# external_strip_v4.net
KiCad netlist of a schematic drawn in EAGLE
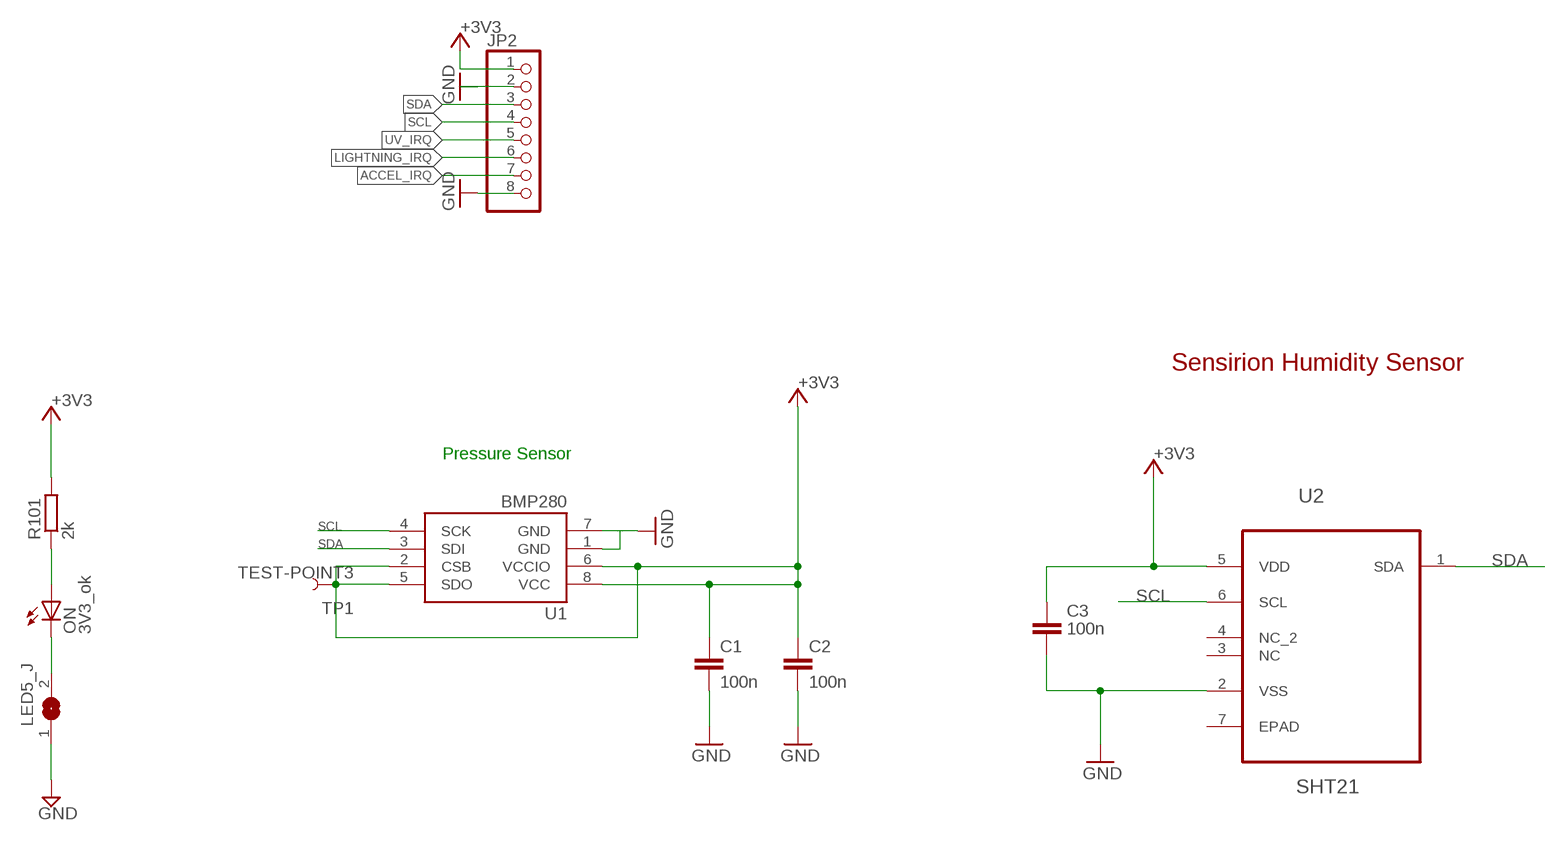
[diagram p0: schematic, sheet 1, part 1 of 2]
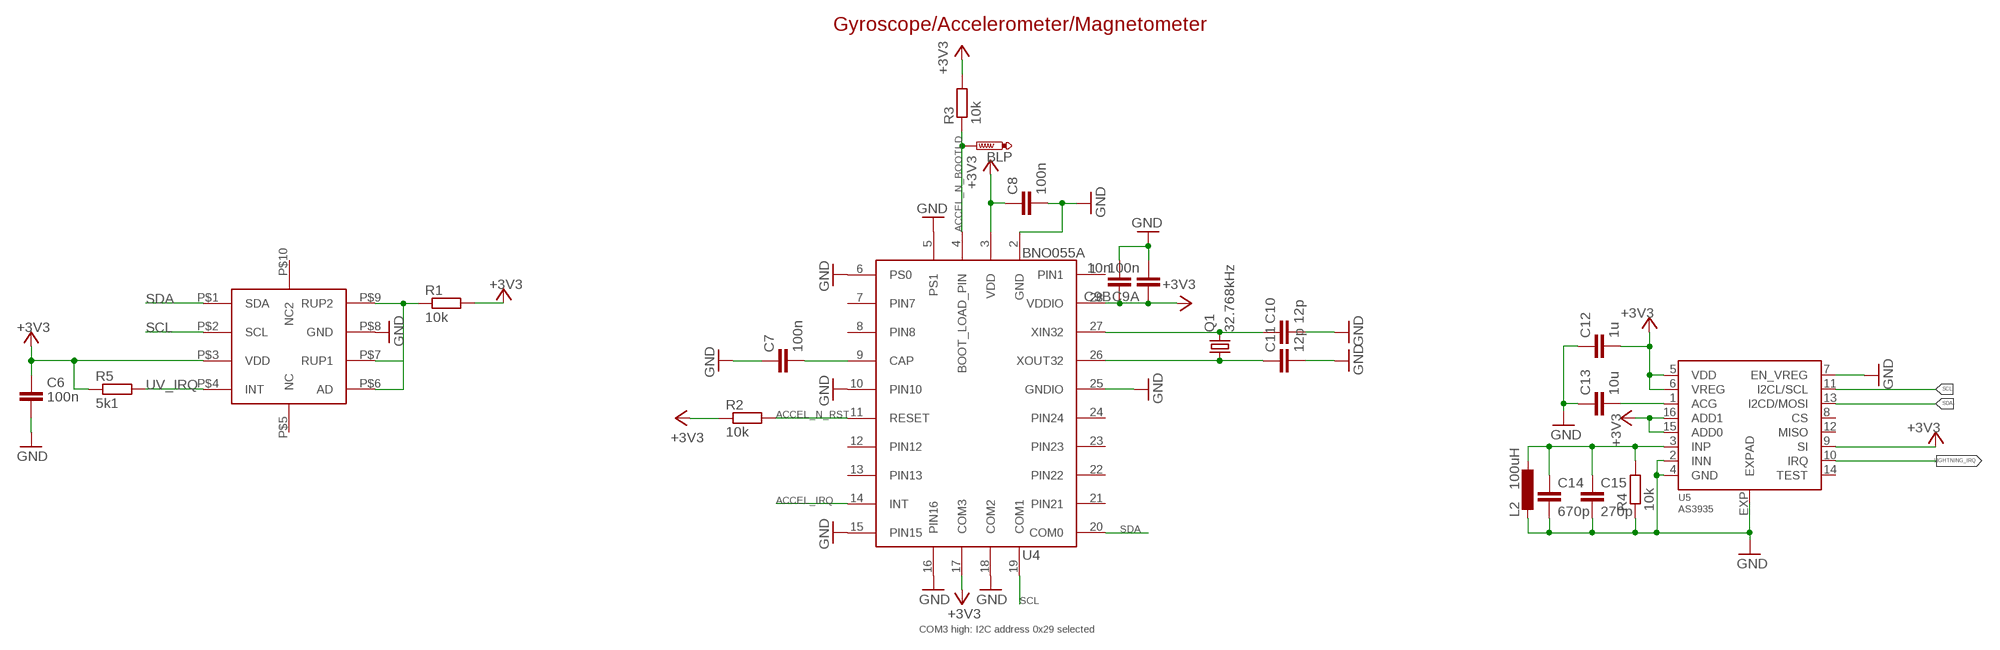
[diagram p1: schematic, sheet 1, part 2 of 2]

(export (version "E")
  (design (tool "Eeschema 10.0.6"))
  (components
    (comp (ref "BLP")
      (value "PTR1B1,27")
      (footprint "eagle-import:B1,27")
      (libsource (lib "eagle-import") (part "PTR1B1,27"))
    )
    (comp (ref "C1")
      (value "100n")
      (footprint "eagle-import:C0603")
      (libsource (lib "eagle-import") (part "C-EUC0603"))
    )
    (comp (ref "C2")
      (value "100n")
      (footprint "eagle-import:C0603")
      (libsource (lib "eagle-import") (part "C-EUC0603"))
    )
    (comp (ref "C3")
      (value "100n")
      (footprint "eagle-import:C0603")
      (libsource (lib "eagle-import") (part "C-EUC0603"))
    )
    (comp (ref "C6")
      (value "100n")
      (footprint "eagle-import:C0603")
      (libsource (lib "eagle-import") (part "C-EUC0603"))
    )
    (comp (ref "C7")
      (value "100n")
      (footprint "eagle-import:C0603")
      (libsource (lib "eagle-import") (part "C-EUC0603"))
    )
    (comp (ref "C8")
      (value "100n")
      (footprint "eagle-import:C0603")
      (libsource (lib "eagle-import") (part "C-EUC0603"))
    )
    (comp (ref "C9A")
      (value "100n")
      (footprint "eagle-import:C0603")
      (libsource (lib "eagle-import") (part "C-EUC0603"))
    )
    (comp (ref "C9B")
      (value "10n")
      (footprint "eagle-import:C0603")
      (libsource (lib "eagle-import") (part "C-EUC0603"))
    )
    (comp (ref "C10")
      (value "12p")
      (footprint "eagle-import:C0603")
      (libsource (lib "eagle-import") (part "C-EUC0603"))
    )
    (comp (ref "C11")
      (value "12p")
      (footprint "eagle-import:C0603")
      (libsource (lib "eagle-import") (part "C-EUC0603"))
    )
    (comp (ref "C12")
      (value "1u")
      (footprint "eagle-import:C0603")
      (libsource (lib "eagle-import") (part "C-EUC0603"))
    )
    (comp (ref "C13")
      (value "10u")
      (footprint "eagle-import:C0603")
      (libsource (lib "eagle-import") (part "C-EUC0603"))
    )
    (comp (ref "C14")
      (value "670p")
      (footprint "eagle-import:C0603")
      (libsource (lib "eagle-import") (part "C-EUC0603"))
    )
    (comp (ref "C15")
      (value "270p")
      (footprint "eagle-import:C0603")
      (libsource (lib "eagle-import") (part "C-EUC0603"))
    )
    (comp (ref "JP2")
      (value "PINHD-1X8")
      (footprint "eagle-import:1X08")
      (libsource (lib "eagle-import") (part "PINHD-1X8"))
    )
    (comp (ref "L2")
      (value "100uH")
      (footprint "eagle-import:COILCRAFT")
      (libsource (lib "eagle-import") (part "COILCRAFT"))
    )
    (comp (ref "LED5_J")
      (value "SJ")
      (footprint "eagle-import:SJ")
      (libsource (lib "eagle-import") (part "SJ"))
    )
    (comp (ref "ON")
      (value "3V3_ok")
      (footprint "eagle-import:CHIPLED_0603")
      (libsource (lib "eagle-import") (part "LEDCHIPLED_0603"))
    )
    (comp (ref "Q1")
      (value "32.768kHz")
      (footprint "eagle-import:FC-12M")
      (libsource (lib "eagle-import") (part "FC-12M"))
    )
    (comp (ref "R1")
      (value "10k")
      (footprint "eagle-import:R0603")
      (libsource (lib "eagle-import") (part "R-EU_R0603"))
    )
    (comp (ref "R2")
      (value "10k")
      (footprint "eagle-import:R0603")
      (libsource (lib "eagle-import") (part "R-EU_R0603"))
    )
    (comp (ref "R3")
      (value "10k")
      (footprint "eagle-import:R0603")
      (libsource (lib "eagle-import") (part "R-EU_R0603"))
    )
    (comp (ref "R4")
      (value "10k")
      (footprint "eagle-import:R0603")
      (libsource (lib "eagle-import") (part "resistor_R-EU_R0603"))
    )
    (comp (ref "R5")
      (value "5k1")
      (footprint "eagle-import:R0603")
      (libsource (lib "eagle-import") (part "R-EU_R0603"))
    )
    (comp (ref "R101")
      (value "2k")
      (footprint "eagle-import:R0603")
      (libsource (lib "eagle-import") (part "R-EU_R0603"))
    )
    (comp (ref "TP1")
      (value "TEST-POINT3")
      (footprint "eagle-import:PAD.03X.03")
      (libsource (lib "eagle-import") (part "TEST-POINT3"))
    )
    (comp (ref "U1")
      (value "BMP280")
      (footprint "eagle-import:LGA8")
      (libsource (lib "eagle-import") (part "BMP280"))
    )
    (comp (ref "U2")
      (value "SHT21")
      (footprint "eagle-import:DFN300X300X110-7N")
      (libsource (lib "eagle-import") (part "SHT21"))
    )
    (comp (ref "U3")
      (value "SI1133")
      (footprint "eagle-import:DFN2X2")
      (libsource (lib "eagle-import") (part "SI1133"))
    )
    (comp (ref "U4")
      (value "BNO055A")
      (footprint "eagle-import:BNO055")
      (libsource (lib "eagle-import") (part "BNO055A"))
    )
    (comp (ref "U5")
      (value "AS3935")
      (footprint "eagle-import:16LDMLPQ")
      (libsource (lib "eagle-import") (part "AS3935"))
    )
  )
  (nets
    (net (code "1") (name "+3V3") (class "Default")
      (node (ref "C1") (pin "1") (pinfunction "1_1") (pintype "passive"))
      (node (ref "C12") (pin "2") (pinfunction "2_2") (pintype "passive"))
      (node (ref "C2") (pin "1") (pinfunction "1_1") (pintype "passive"))
      (node (ref "C3") (pin "1") (pinfunction "1_1") (pintype "passive"))
      (node (ref "C6") (pin "1") (pinfunction "1_1") (pintype "passive"))
      (node (ref "C8") (pin "1") (pinfunction "1_1") (pintype "passive"))
      (node (ref "C9A") (pin "1") (pinfunction "1_1") (pintype "passive"))
      (node (ref "C9B") (pin "1") (pinfunction "1_1") (pintype "passive"))
      (node (ref "JP2") (pin "1") (pinfunction "1_1") (pintype "passive"))
      (node (ref "R1") (pin "2") (pinfunction "2_2") (pintype "passive"))
      (node (ref "R101") (pin "2") (pinfunction "2_2") (pintype "passive"))
      (node (ref "R2") (pin "1") (pinfunction "1_1") (pintype "passive"))
      (node (ref "R3") (pin "2") (pinfunction "2_2") (pintype "passive"))
      (node (ref "R5") (pin "1") (pinfunction "1_1") (pintype "passive"))
      (node (ref "TP1") (pin "P$1") (pinfunction "1_P$1") (pintype "bidirectional"))
      (node (ref "U1") (pin "2") (pinfunction "CSB_2") (pintype "input"))
      (node (ref "U1") (pin "5") (pinfunction "SDO_5") (pintype "bidirectional"))
      (node (ref "U1") (pin "6") (pinfunction "VCCIO_6") (pintype "power_in"))
      (node (ref "U1") (pin "8") (pinfunction "VCC_8") (pintype "power_in"))
      (node (ref "U2") (pin "5") (pinfunction "VDD_5") (pintype "power_in"))
      (node (ref "U3") (pin "P$3") (pinfunction "VDD_P$3") (pintype "bidirectional"))
      (node (ref "U4") (pin "17") (pinfunction "COM3_17") (pintype "bidirectional"))
      (node (ref "U4") (pin "28") (pinfunction "VDDIO_28") (pintype "bidirectional"))
      (node (ref "U4") (pin "3") (pinfunction "VDD_3") (pintype "bidirectional"))
      (node (ref "U5") (pin "15") (pinfunction "ADD0_15") (pintype "bidirectional"))
      (node (ref "U5") (pin "16") (pinfunction "ADD1_16") (pintype "bidirectional"))
      (node (ref "U5") (pin "5") (pinfunction "VDD_5") (pintype "bidirectional"))
      (node (ref "U5") (pin "6") (pinfunction "VREG_6") (pintype "bidirectional"))
      (node (ref "U5") (pin "9") (pinfunction "SI_9") (pintype "bidirectional"))
    )
    (net (code "2") (name "/ACCEL_N_BOOTLD") (class "Default")
      (node (ref "BLP") (pin "TP") (pinfunction "TP_TP") (pintype "input"))
      (node (ref "R3") (pin "1") (pinfunction "1_1") (pintype "passive"))
      (node (ref "U4") (pin "4") (pinfunction "BOOT_LOAD_PIN_4") (pintype "bidirectional"))
    )
    (net (code "3") (name "/ACCEL_N_RST") (class "Default")
      (node (ref "R2") (pin "2") (pinfunction "2_2") (pintype "passive"))
      (node (ref "U4") (pin "11") (pinfunction "RESET_11") (pintype "bidirectional"))
    )
    (net (code "4") (name "ACCEL_IRQ") (class "Default")
      (node (ref "JP2") (pin "7") (pinfunction "7_7") (pintype "passive"))
      (node (ref "U4") (pin "14") (pinfunction "INT_14") (pintype "bidirectional"))
    )
    (net (code "5") (name "GND") (class "Default")
      (node (ref "C1") (pin "2") (pinfunction "2_2") (pintype "passive"))
      (node (ref "C10") (pin "2") (pinfunction "2_2") (pintype "passive"))
      (node (ref "C11") (pin "2") (pinfunction "2_2") (pintype "passive"))
      (node (ref "C12") (pin "1") (pinfunction "1_1") (pintype "passive"))
      (node (ref "C13") (pin "1") (pinfunction "1_1") (pintype "passive"))
      (node (ref "C14") (pin "2") (pinfunction "2_2") (pintype "passive"))
      (node (ref "C15") (pin "2") (pinfunction "2_2") (pintype "passive"))
      (node (ref "C2") (pin "2") (pinfunction "2_2") (pintype "passive"))
      (node (ref "C3") (pin "2") (pinfunction "2_2") (pintype "passive"))
      (node (ref "C6") (pin "2") (pinfunction "2_2") (pintype "passive"))
      (node (ref "C7") (pin "1") (pinfunction "1_1") (pintype "passive"))
      (node (ref "C8") (pin "2") (pinfunction "2_2") (pintype "passive"))
      (node (ref "C9A") (pin "2") (pinfunction "2_2") (pintype "passive"))
      (node (ref "C9B") (pin "2") (pinfunction "2_2") (pintype "passive"))
      (node (ref "JP2") (pin "2") (pinfunction "2_2") (pintype "passive"))
      (node (ref "JP2") (pin "8") (pinfunction "8_8") (pintype "passive"))
      (node (ref "L2") (pin "2") (pinfunction "2_2") (pintype "passive"))
      (node (ref "LED5_J") (pin "1") (pinfunction "1_1") (pintype "passive"))
      (node (ref "R4") (pin "1") (pinfunction "1_1") (pintype "passive"))
      (node (ref "U1") (pin "1") (pinfunction "GND_1") (pintype "power_in"))
      (node (ref "U1") (pin "7") (pinfunction "GND_7") (pintype "power_in"))
      (node (ref "U2") (pin "2") (pinfunction "VSS_2") (pintype "power_in"))
      (node (ref "U3") (pin "P$8") (pinfunction "GND_P$8") (pintype "bidirectional"))
      (node (ref "U4") (pin "10") (pinfunction "PIN10_10") (pintype "bidirectional"))
      (node (ref "U4") (pin "15") (pinfunction "PIN15_15") (pintype "bidirectional"))
      (node (ref "U4") (pin "16") (pinfunction "PIN16_16") (pintype "bidirectional"))
      (node (ref "U4") (pin "18") (pinfunction "COM2_18") (pintype "bidirectional"))
      (node (ref "U4") (pin "2") (pinfunction "GND_2") (pintype "bidirectional"))
      (node (ref "U4") (pin "25") (pinfunction "GNDIO_25") (pintype "bidirectional"))
      (node (ref "U4") (pin "5") (pinfunction "PS1_5") (pintype "bidirectional"))
      (node (ref "U4") (pin "6") (pinfunction "PS0_6") (pintype "bidirectional"))
      (node (ref "U5") (pin "2") (pinfunction "INN_2") (pintype "bidirectional"))
      (node (ref "U5") (pin "4") (pinfunction "GND_4") (pintype "bidirectional"))
      (node (ref "U5") (pin "7") (pinfunction "EN_VREG_7") (pintype "bidirectional"))
      (node (ref "U5") (pin "EXP") (pinfunction "EXPAD_EXP") (pintype "bidirectional"))
    )
    (net (code "6") (name "LIGHTNING_IRQ") (class "Default")
      (node (ref "JP2") (pin "6") (pinfunction "6_6") (pintype "passive"))
      (node (ref "U5") (pin "10") (pinfunction "IRQ_10") (pintype "bidirectional"))
    )
    (net (code "7") (name "Net-(LED5_J-Pad2)") (class "Default")
      (node (ref "LED5_J") (pin "2") (pinfunction "2_2") (pintype "passive"))
      (node (ref "ON") (pin "C") (pinfunction "C_C") (pintype "passive"))
    )
    (net (code "8") (name "Net-(ON-PadA)") (class "Default")
      (node (ref "ON") (pin "A") (pinfunction "A_A") (pintype "passive"))
      (node (ref "R101") (pin "1") (pinfunction "1_1") (pintype "passive"))
    )
    (net (code "9") (name "Net-(U3-AD)") (class "Default")
      (node (ref "R1") (pin "1") (pinfunction "1_1") (pintype "passive"))
      (node (ref "U3") (pin "P$6") (pinfunction "AD_P$6") (pintype "bidirectional"))
      (node (ref "U3") (pin "P$7") (pinfunction "RUP1_P$7") (pintype "bidirectional"))
      (node (ref "U3") (pin "P$9") (pinfunction "RUP2_P$9") (pintype "bidirectional"))
    )
    (net (code "10") (name "Net-(U4-CAP)") (class "Default")
      (node (ref "C7") (pin "2") (pinfunction "2_2") (pintype "passive"))
      (node (ref "U4") (pin "9") (pinfunction "CAP_9") (pintype "bidirectional"))
    )
    (net (code "11") (name "Net-(U4-XIN32)") (class "Default")
      (node (ref "C10") (pin "1") (pinfunction "1_1") (pintype "passive"))
      (node (ref "Q1") (pin "2") (pinfunction "2_2") (pintype "passive"))
      (node (ref "U4") (pin "27") (pinfunction "XIN32_27") (pintype "bidirectional"))
    )
    (net (code "12") (name "Net-(U4-XOUT32)") (class "Default")
      (node (ref "C11") (pin "1") (pinfunction "1_1") (pintype "passive"))
      (node (ref "Q1") (pin "1") (pinfunction "1_1") (pintype "passive"))
      (node (ref "U4") (pin "26") (pinfunction "XOUT32_26") (pintype "bidirectional"))
    )
    (net (code "13") (name "Net-(U5-ACG)") (class "Default")
      (node (ref "C13") (pin "2") (pinfunction "2_2") (pintype "passive"))
      (node (ref "U5") (pin "1") (pinfunction "ACG_1") (pintype "bidirectional"))
    )
    (net (code "14") (name "Net-(U5-INP)") (class "Default")
      (node (ref "C14") (pin "1") (pinfunction "1_1") (pintype "passive"))
      (node (ref "C15") (pin "1") (pinfunction "1_1") (pintype "passive"))
      (node (ref "L2") (pin "1") (pinfunction "1_1") (pintype "passive"))
      (node (ref "R4") (pin "2") (pinfunction "2_2") (pintype "passive"))
      (node (ref "U5") (pin "3") (pinfunction "INP_3") (pintype "bidirectional"))
    )
    (net (code "15") (name "SCL") (class "Default")
      (node (ref "JP2") (pin "4") (pinfunction "4_4") (pintype "passive"))
      (node (ref "U1") (pin "4") (pinfunction "SCK_4") (pintype "bidirectional"))
      (node (ref "U2") (pin "6") (pinfunction "SCL_6") (pintype "input"))
      (node (ref "U3") (pin "P$2") (pinfunction "SCL_P$2") (pintype "bidirectional"))
      (node (ref "U4") (pin "19") (pinfunction "COM1_19") (pintype "bidirectional"))
      (node (ref "U5") (pin "11") (pinfunction "I2CL/SCL_11") (pintype "bidirectional"))
    )
    (net (code "16") (name "SDA") (class "Default")
      (node (ref "JP2") (pin "3") (pinfunction "3_3") (pintype "passive"))
      (node (ref "U1") (pin "3") (pinfunction "SDI_3") (pintype "bidirectional"))
      (node (ref "U2") (pin "1") (pinfunction "SDA_1") (pintype "bidirectional"))
      (node (ref "U3") (pin "P$1") (pinfunction "SDA_P$1") (pintype "bidirectional"))
      (node (ref "U4") (pin "20") (pinfunction "COM0_20") (pintype "bidirectional"))
      (node (ref "U5") (pin "13") (pinfunction "I2CD/MOSI_13") (pintype "bidirectional"))
    )
    (net (code "17") (name "UV_IRQ") (class "Default")
      (node (ref "JP2") (pin "5") (pinfunction "5_5") (pintype "passive"))
      (node (ref "R5") (pin "2") (pinfunction "2_2") (pintype "passive"))
      (node (ref "U3") (pin "P$4") (pinfunction "INT_P$4") (pintype "bidirectional"))
    )
    (net (code "18") (name "unconnected-(U2-EPAD-Pad7)") (class "Default")
      (node (ref "U2") (pin "7") (pinfunction "EPAD_7") (pintype "passive"))
    )
    (net (code "19") (name "unconnected-(U2-NC-Pad3)") (class "Default")
      (node (ref "U2") (pin "3") (pinfunction "NC_3") (pintype "no_connect"))
    )
    (net (code "20") (name "unconnected-(U2-NC_2-Pad4)") (class "Default")
      (node (ref "U2") (pin "4") (pinfunction "NC_2_4") (pintype "no_connect"))
    )
    (net (code "21") (name "unconnected-(U3-NC-PadP$5)") (class "Default")
      (node (ref "U3") (pin "P$5") (pinfunction "NC_P$5") (pintype "bidirectional"))
    )
    (net (code "22") (name "unconnected-(U3-NC2-PadP$10)") (class "Default")
      (node (ref "U3") (pin "P$10") (pinfunction "NC2_P$10") (pintype "bidirectional"))
    )
    (net (code "23") (name "unconnected-(U4-PIN1-Pad1)") (class "Default")
      (node (ref "U4") (pin "1") (pinfunction "PIN1_1") (pintype "bidirectional"))
    )
    (net (code "24") (name "unconnected-(U4-PIN7-Pad7)") (class "Default")
      (node (ref "U4") (pin "7") (pinfunction "PIN7_7") (pintype "bidirectional"))
    )
    (net (code "25") (name "unconnected-(U4-PIN8-Pad8)") (class "Default")
      (node (ref "U4") (pin "8") (pinfunction "PIN8_8") (pintype "bidirectional"))
    )
    (net (code "26") (name "unconnected-(U4-PIN12-Pad12)") (class "Default")
      (node (ref "U4") (pin "12") (pinfunction "PIN12_12") (pintype "bidirectional"))
    )
    (net (code "27") (name "unconnected-(U4-PIN13-Pad13)") (class "Default")
      (node (ref "U4") (pin "13") (pinfunction "PIN13_13") (pintype "bidirectional"))
    )
    (net (code "28") (name "unconnected-(U4-PIN21-Pad21)") (class "Default")
      (node (ref "U4") (pin "21") (pinfunction "PIN21_21") (pintype "bidirectional"))
    )
    (net (code "29") (name "unconnected-(U4-PIN22-Pad22)") (class "Default")
      (node (ref "U4") (pin "22") (pinfunction "PIN22_22") (pintype "bidirectional"))
    )
    (net (code "30") (name "unconnected-(U4-PIN23-Pad23)") (class "Default")
      (node (ref "U4") (pin "23") (pinfunction "PIN23_23") (pintype "bidirectional"))
    )
    (net (code "31") (name "unconnected-(U4-PIN24-Pad24)") (class "Default")
      (node (ref "U4") (pin "24") (pinfunction "PIN24_24") (pintype "bidirectional"))
    )
    (net (code "32") (name "unconnected-(U5-CS-Pad8)") (class "Default")
      (node (ref "U5") (pin "8") (pinfunction "CS_8") (pintype "bidirectional"))
    )
    (net (code "33") (name "unconnected-(U5-MISO-Pad12)") (class "Default")
      (node (ref "U5") (pin "12") (pinfunction "MISO_12") (pintype "bidirectional"))
    )
    (net (code "34") (name "unconnected-(U5-TEST-Pad14)") (class "Default")
      (node (ref "U5") (pin "14") (pinfunction "TEST_14") (pintype "passive"))
    )
  )
)
